# Sheet2_MCU_Digital.net
KiCad netlist of a schematic drawn in Altium Designer
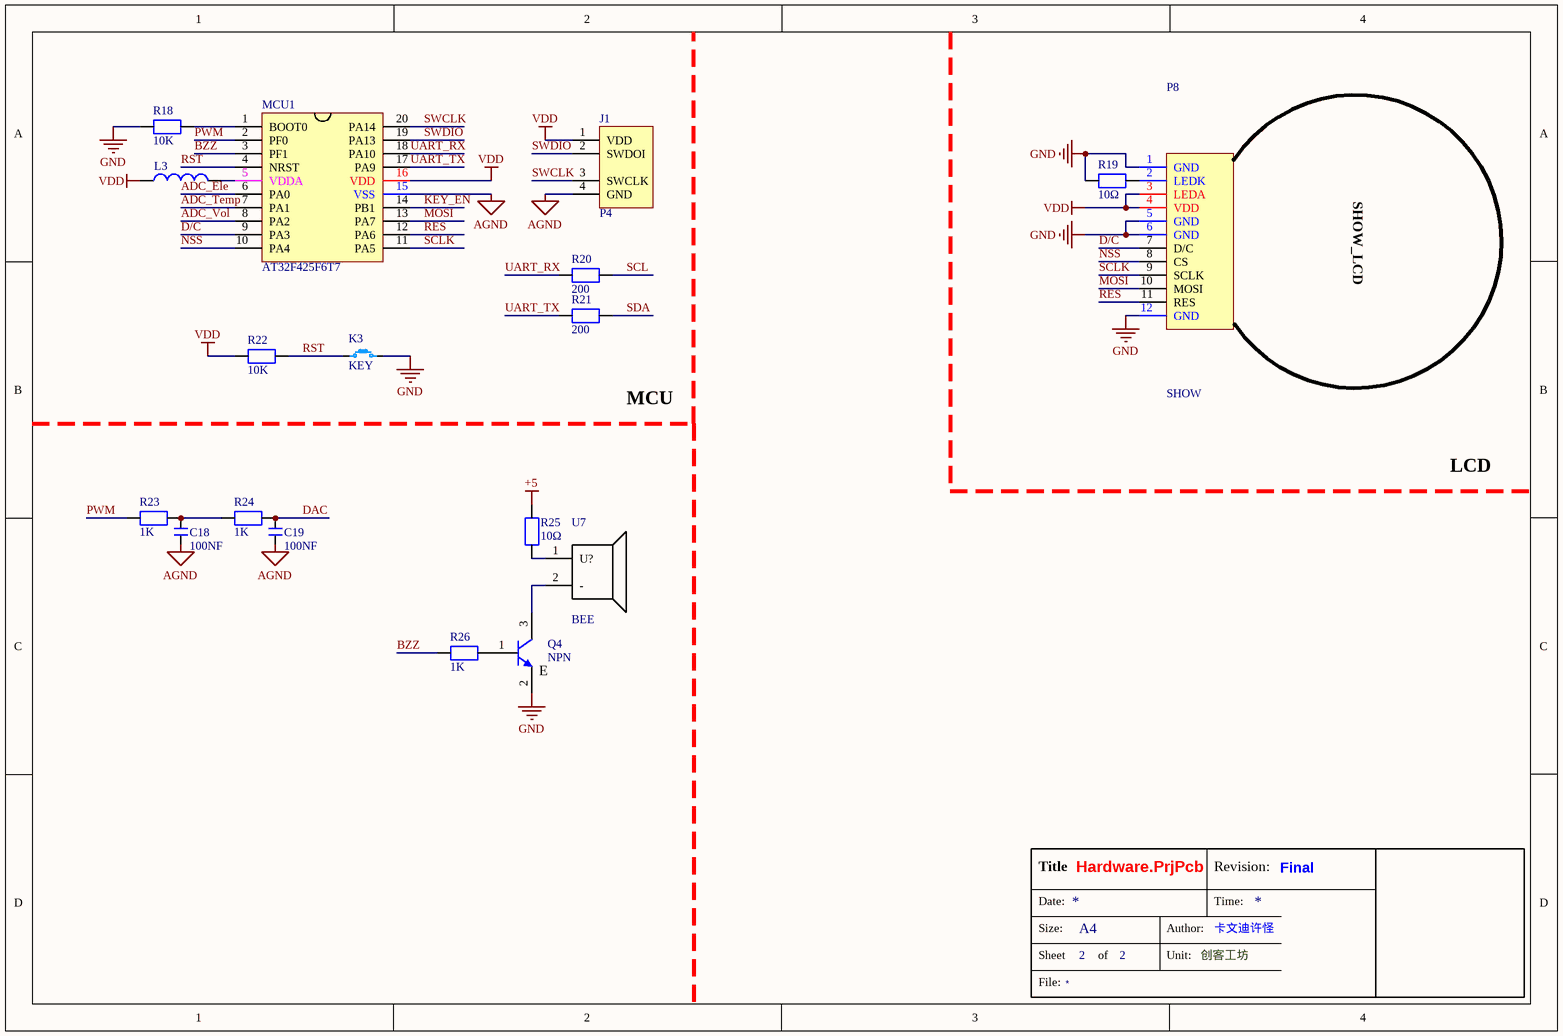
[diagram p0: Sheet2_MCU_Digital.SchDoc]

(export (version "E")
  (design (tool "Eeschema 10.0.6"))
  (components
    (comp (ref "C18")
      (value "100NF")
      (footprint "CAP_0603")
      (description "CAP  12~50V")
      (libsource (lib "User") (part "CAP"))
    )
    (comp (ref "C19")
      (value "100NF")
      (footprint "CAP_0603")
      (description "CAP  12~50V")
      (libsource (lib "User") (part "CAP"))
    )
    (comp (ref "J1")
      (value "P4")
      (footprint "XH2.54-WS-4P")
      (description "Header")
      (libsource (lib "User") (part "SWD"))
    )
    (comp (ref "K3")
      (value "KEY")
      (footprint "KEY_SMD-4P")
      (description "Key")
      (libsource (lib "User") (part "KEY"))
    )
    (comp (ref "L3")
      (value "2.2UH")
      (footprint "Inductor_0603")
      (description "Inductor")
      (fields (field (name "PUBLISHER") "Altium Limited"))
      (libsource (lib "User") (part "Inductor"))
    )
    (comp (ref "MCU1")
      (value "AT32F425F6T7")
      (footprint "TSSOP_20")
      (description "MCU")
      (libsource (lib "User") (part "AT32F425F6T7"))
    )
    (comp (ref "P8")
      (value "SHOW")
      (footprint "LCD_1.28")
      (description "LCD-circle-1.28")
      (libsource (lib "User") (part "LCD_circle"))
    )
    (comp (ref "Q4") (value "NPN") (footprint "SOT23_3") (libsource (lib "User") (part "NPN")))
    (comp (ref "R18")
      (value "10K")
      (footprint "RESC_0603_2")
      (description "RES 贴片")
      (libsource (lib "User") (part "RES"))
    )
    (comp (ref "R19")
      (value "10Ω")
      (footprint "RESC_0603_2")
      (description "RES 贴片")
      (libsource (lib "User") (part "RES"))
    )
    (comp (ref "R20")
      (value "200")
      (footprint "RESC_0603_2")
      (description "RES 贴片")
      (libsource (lib "User") (part "RES"))
    )
    (comp (ref "R21")
      (value "200")
      (footprint "RESC_0603_2")
      (description "RES 贴片")
      (libsource (lib "User") (part "RES"))
    )
    (comp (ref "R22")
      (value "10K")
      (footprint "RESC_0603_2")
      (description "RES 贴片")
      (libsource (lib "User") (part "RES"))
    )
    (comp (ref "R23")
      (value "1K")
      (footprint "RESC_0603_2")
      (description "RES 贴片")
      (libsource (lib "User") (part "RES"))
    )
    (comp (ref "R24")
      (value "1K")
      (footprint "RESC_0603_2")
      (description "RES 贴片")
      (libsource (lib "User") (part "RES"))
    )
    (comp (ref "R25")
      (value "10Ω")
      (footprint "RESC_0603_2")
      (description "RES 贴片")
      (libsource (lib "User") (part "RES"))
    )
    (comp (ref "R26")
      (value "1K")
      (footprint "RESC_0603_2")
      (description "RES 贴片")
      (libsource (lib "User") (part "RES"))
    )
    (comp (ref "U7") (value "BEE") (footprint "SMD402") (libsource (lib "User") (part "BZZ")))
  )
  (nets
    (net (code "1") (name "+5") (class "Default")
      (node (ref "R25") (pin "2") (pinfunction "2_2") (pintype "passive"))
    )
    (net (code "2") (name "/ADC_Ele") (class "Default")
      (node (ref "MCU1") (pin "6") (pinfunction "PA0_6") (pintype "passive"))
    )
    (net (code "3") (name "/ADC_Temp") (class "Default")
      (node (ref "MCU1") (pin "7") (pinfunction "PA1_7") (pintype "passive"))
    )
    (net (code "4") (name "/ADC_Vol") (class "Default")
      (node (ref "MCU1") (pin "8") (pinfunction "PA2_8") (pintype "passive"))
    )
    (net (code "5") (name "/BZZ") (class "Default")
      (node (ref "MCU1") (pin "3") (pinfunction "PF1_3") (pintype "passive"))
      (node (ref "R26") (pin "2") (pinfunction "2_2") (pintype "passive"))
    )
    (net (code "6") (name "/DAC") (class "Default")
      (node (ref "C19") (pin "2") (pinfunction "0_2") (pintype "passive"))
      (node (ref "R24") (pin "1") (pinfunction "1_1") (pintype "passive"))
    )
    (net (code "7") (name "/D{slash}C") (class "Default")
      (node (ref "MCU1") (pin "9") (pinfunction "PA3_9") (pintype "passive"))
      (node (ref "P8") (pin "7") (pinfunction "D/C_7") (pintype "passive"))
    )
    (net (code "8") (name "/KEY_EN") (class "Default")
      (node (ref "MCU1") (pin "14") (pinfunction "PB1_14") (pintype "passive"))
    )
    (net (code "9") (name "/MOSI") (class "Default")
      (node (ref "MCU1") (pin "13") (pinfunction "PA7_13") (pintype "passive"))
      (node (ref "P8") (pin "10") (pinfunction "MOSI_10") (pintype "passive"))
    )
    (net (code "10") (name "/NSS") (class "Default")
      (node (ref "MCU1") (pin "10") (pinfunction "PA4_10") (pintype "passive"))
      (node (ref "P8") (pin "8") (pinfunction "CS_8") (pintype "passive"))
    )
    (net (code "11") (name "/PWM") (class "Default")
      (node (ref "MCU1") (pin "2") (pinfunction "PF0_2") (pintype "passive"))
      (node (ref "R23") (pin "2") (pinfunction "2_2") (pintype "passive"))
    )
    (net (code "12") (name "/RES") (class "Default")
      (node (ref "MCU1") (pin "12") (pinfunction "PA6_12") (pintype "passive"))
      (node (ref "P8") (pin "11") (pinfunction "RES_11") (pintype "passive"))
    )
    (net (code "13") (name "/RST") (class "Default")
      (node (ref "K3") (pin "2") (pintype "passive"))
      (node (ref "MCU1") (pin "4") (pinfunction "NRST_4") (pintype "passive"))
      (node (ref "R22") (pin "1") (pinfunction "1_1") (pintype "passive"))
    )
    (net (code "14") (name "/SCL") (class "Default")
      (node (ref "R20") (pin "2") (pinfunction "2_2") (pintype "passive"))
    )
    (net (code "15") (name "/SCLK") (class "Default")
      (node (ref "MCU1") (pin "11") (pinfunction "PA5_11") (pintype "passive"))
      (node (ref "P8") (pin "9") (pinfunction "SCLK_9") (pintype "passive"))
    )
    (net (code "16") (name "/SDA") (class "Default")
      (node (ref "R21") (pin "2") (pinfunction "2_2") (pintype "passive"))
    )
    (net (code "17") (name "/SWCLK") (class "Default")
      (node (ref "J1") (pin "3") (pinfunction "SWCLK_3") (pintype "passive"))
      (node (ref "MCU1") (pin "20") (pinfunction "PA14_20") (pintype "passive"))
    )
    (net (code "18") (name "/SWDIO") (class "Default")
      (node (ref "J1") (pin "2") (pinfunction "SWDOI_2") (pintype "passive"))
      (node (ref "MCU1") (pin "19") (pinfunction "PA13_19") (pintype "passive"))
    )
    (net (code "19") (name "/UART_RX") (class "Default")
      (node (ref "MCU1") (pin "18") (pinfunction "PA10_18") (pintype "passive"))
      (node (ref "R20") (pin "1") (pinfunction "1_1") (pintype "passive"))
    )
    (net (code "20") (name "/UART_TX") (class "Default")
      (node (ref "MCU1") (pin "17") (pinfunction "PA9_17") (pintype "passive"))
      (node (ref "R21") (pin "1") (pinfunction "1_1") (pintype "passive"))
    )
    (net (code "21") (name "AGND") (class "Default")
      (node (ref "C18") (pin "1") (pinfunction "0_1") (pintype "passive"))
      (node (ref "C19") (pin "1") (pinfunction "0_1") (pintype "passive"))
      (node (ref "J1") (pin "4") (pinfunction "GND_4") (pintype "passive"))
      (node (ref "MCU1") (pin "15") (pinfunction "VSS_15") (pintype "passive"))
    )
    (net (code "22") (name "GND") (class "Default")
      (node (ref "K3") (pin "1") (pintype "passive"))
      (node (ref "P8") (pin "1") (pinfunction "GND_1") (pintype "passive"))
      (node (ref "P8") (pin "12") (pinfunction "GND_12") (pintype "passive"))
      (node (ref "P8") (pin "5") (pinfunction "GND_5") (pintype "passive"))
      (node (ref "P8") (pin "6") (pinfunction "GND_6") (pintype "passive"))
      (node (ref "Q4") (pin "2") (pinfunction "E_2") (pintype "passive"))
      (node (ref "R18") (pin "2") (pinfunction "2_2") (pintype "passive"))
      (node (ref "R19") (pin "2") (pinfunction "2_2") (pintype "passive"))
    )
    (net (code "23") (name "Net-(C18-0-Pad2)") (class "Default")
      (node (ref "C18") (pin "2") (pinfunction "0_2") (pintype "passive"))
      (node (ref "R23") (pin "1") (pinfunction "1_1") (pintype "passive"))
      (node (ref "R24") (pin "2") (pinfunction "2_2") (pintype "passive"))
    )
    (net (code "24") (name "Net-(MCU1-BOOT0)") (class "Default")
      (node (ref "MCU1") (pin "1") (pinfunction "BOOT0_1") (pintype "passive"))
      (node (ref "R18") (pin "1") (pinfunction "1_1") (pintype "passive"))
    )
    (net (code "25") (name "Net-(MCU1-VDDA)") (class "Default")
      (node (ref "L3") (pin "2") (pinfunction "2_2") (pintype "passive"))
      (node (ref "MCU1") (pin "5") (pinfunction "VDDA_5") (pintype "passive"))
    )
    (net (code "26") (name "Net-(P8-LEDK)") (class "Default")
      (node (ref "P8") (pin "2") (pinfunction "LEDK_2") (pintype "passive"))
      (node (ref "R19") (pin "1") (pinfunction "1_1") (pintype "passive"))
    )
    (net (code "27") (name "Net-(Q4-B)") (class "Default")
      (node (ref "Q4") (pin "1") (pinfunction "B_1") (pintype "passive"))
      (node (ref "R26") (pin "1") (pinfunction "1_1") (pintype "passive"))
    )
    (net (code "28") (name "Net-(Q4-C)") (class "Default")
      (node (ref "Q4") (pin "3") (pinfunction "C_3") (pintype "passive"))
      (node (ref "U7") (pin "2") (pinfunction "-_2") (pintype "passive"))
    )
    (net (code "29") (name "Net-(U7-U?)") (class "Default")
      (node (ref "R25") (pin "1") (pinfunction "1_1") (pintype "passive"))
      (node (ref "U7") (pin "1") (pinfunction "U?_1") (pintype "passive"))
    )
    (net (code "30") (name "VDD") (class "Default")
      (node (ref "J1") (pin "1") (pinfunction "VDD_1") (pintype "passive"))
      (node (ref "L3") (pin "1") (pinfunction "1_1") (pintype "passive"))
      (node (ref "MCU1") (pin "16") (pinfunction "VDD_16") (pintype "passive"))
      (node (ref "P8") (pin "3") (pinfunction "LEDA_3") (pintype "passive"))
      (node (ref "P8") (pin "4") (pinfunction "VDD_4") (pintype "passive"))
      (node (ref "R22") (pin "2") (pinfunction "2_2") (pintype "passive"))
    )
  )
)
